# Switch-12v-PWM-4Ch.net
KiCad netlist of a schematic drawn in EAGLE
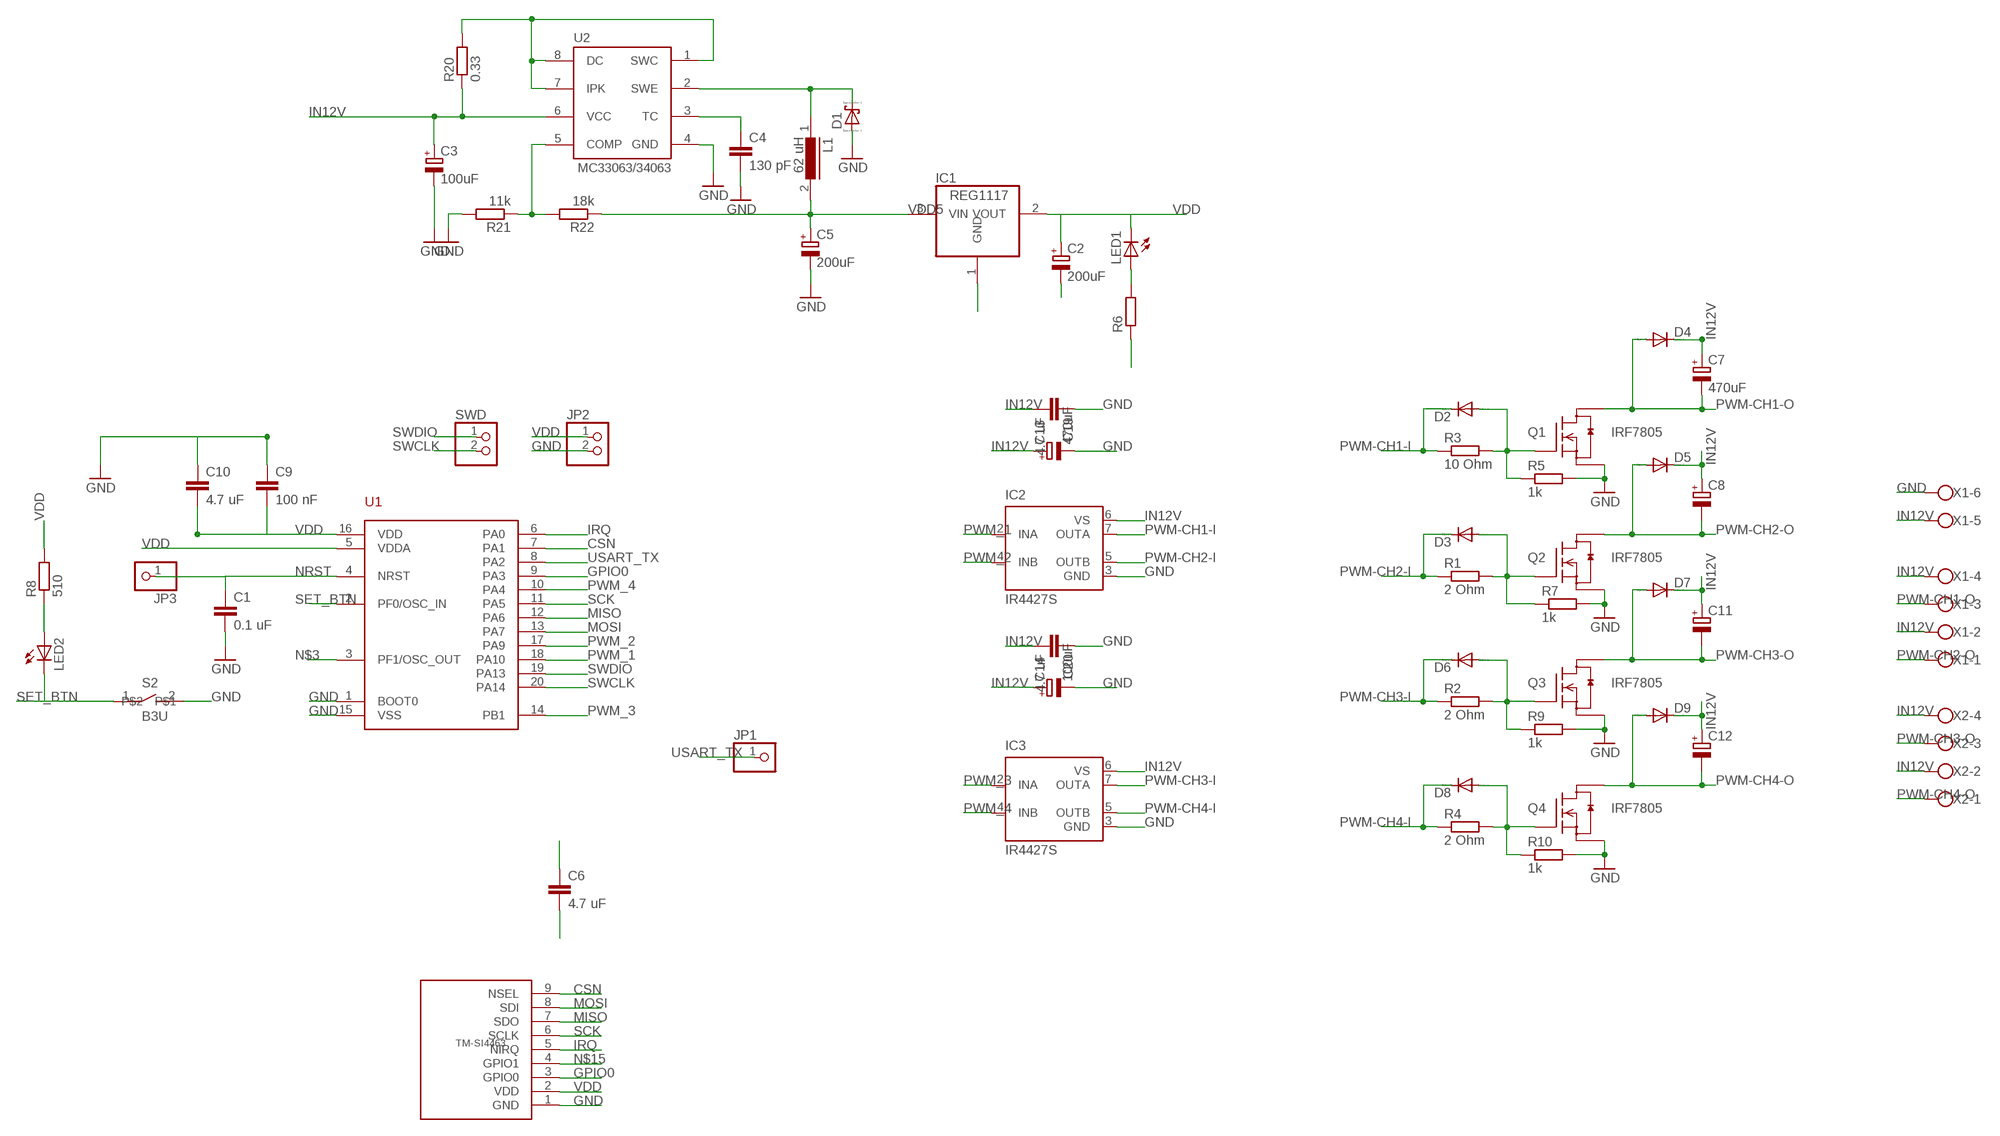
[diagram p0: schematic, sheet 1]

(export (version "E")
  (design (tool "Eeschema 10.0.6"))
  (components
    (comp (ref "C1")
      (value "0.1 uF")
      (footprint "eagle-import:C0805")
      (libsource (lib "eagle-import") (part "C-EUC0805"))
    )
    (comp (ref "C2")
      (value "200uF")
      (footprint "eagle-import:SMC_C")
      (libsource (lib "eagle-import") (part "CPOL-EUSMCC"))
    )
    (comp (ref "C3")
      (value "100uF")
      (footprint "eagle-import:SMC_C")
      (libsource (lib "eagle-import") (part "CPOL-EUSMCC"))
    )
    (comp (ref "C4")
      (value "130 pF")
      (footprint "eagle-import:C0805")
      (libsource (lib "eagle-import") (part "C-EUC0805"))
    )
    (comp (ref "C5")
      (value "200uF")
      (footprint "eagle-import:SMC_C")
      (libsource (lib "eagle-import") (part "CPOL-EUSMCC"))
    )
    (comp (ref "C6")
      (value "4.7 uF")
      (footprint "eagle-import:C0805")
      (libsource (lib "eagle-import") (part "C-EUC0805"))
    )
    (comp (ref "C7")
      (value "470uF")
      (footprint "eagle-import:E5-8,5")
      (libsource (lib "eagle-import") (part "CPOL-EUE5-8.5"))
    )
    (comp (ref "C8")
      (value "CPOL-EUE5-8.5")
      (footprint "eagle-import:E5-8,5")
      (libsource (lib "eagle-import") (part "CPOL-EUE5-8.5"))
    )
    (comp (ref "C9")
      (value "100 nF")
      (footprint "eagle-import:C0805")
      (libsource (lib "eagle-import") (part "C-EUC0805"))
    )
    (comp (ref "C10")
      (value "4.7 uF")
      (footprint "eagle-import:C0805")
      (libsource (lib "eagle-import") (part "C-EUC0805"))
    )
    (comp (ref "C11")
      (value "CPOL-EUE5-8.5")
      (footprint "eagle-import:E5-8,5")
      (libsource (lib "eagle-import") (part "CPOL-EUE5-8.5"))
    )
    (comp (ref "C12")
      (value "CPOL-EUE5-8.5")
      (footprint "eagle-import:E5-8,5")
      (libsource (lib "eagle-import") (part "CPOL-EUE5-8.5"))
    )
    (comp (ref "C13")
      (value "470uF")
      (footprint "eagle-import:085CS_1AR")
      (libsource (lib "eagle-import") (part "CPOL-EU085CS-1AR"))
    )
    (comp (ref "C14")
      (value "100uF")
      (footprint "eagle-import:085CS_1AR")
      (libsource (lib "eagle-import") (part "CPOL-EU085CS-1AR"))
    )
    (comp (ref "C19")
      (value "4.7 uF")
      (footprint "eagle-import:C0805")
      (libsource (lib "eagle-import") (part "C-EUC0805"))
    )
    (comp (ref "C20")
      (value "4.7 uF")
      (footprint "eagle-import:C0805")
      (libsource (lib "eagle-import") (part "C-EUC0805"))
    )
    (comp (ref "D1")
      (value "SCHOTTKY-DIODE")
      (footprint "eagle-import:DIODE_SMB")
      (libsource (lib "eagle-import") (part "SCHOTTKY-DIODE"))
    )
    (comp (ref "D2")
      (value "DIODE-DO214BA")
      (footprint "eagle-import:DO214BA")
      (libsource (lib "eagle-import") (part "DIODE-DO214BA"))
    )
    (comp (ref "D3")
      (value "DIODE-DO214BA")
      (footprint "eagle-import:DO214BA")
      (libsource (lib "eagle-import") (part "DIODE-DO214BA"))
    )
    (comp (ref "D4")
      (value "DIODE-DO214BA")
      (footprint "eagle-import:DO214BA")
      (libsource (lib "eagle-import") (part "DIODE-DO214BA"))
    )
    (comp (ref "D5")
      (value "DIODE-DO214BA")
      (footprint "eagle-import:DO214BA")
      (libsource (lib "eagle-import") (part "DIODE-DO214BA"))
    )
    (comp (ref "D6")
      (value "DIODE-DO214BA")
      (footprint "eagle-import:DO214BA")
      (libsource (lib "eagle-import") (part "DIODE-DO214BA"))
    )
    (comp (ref "D7")
      (value "DIODE-DO214BA")
      (footprint "eagle-import:DO214BA")
      (libsource (lib "eagle-import") (part "DIODE-DO214BA"))
    )
    (comp (ref "D8")
      (value "DIODE-DO214BA")
      (footprint "eagle-import:DO214BA")
      (libsource (lib "eagle-import") (part "DIODE-DO214BA"))
    )
    (comp (ref "D9")
      (value "DIODE-DO214BA")
      (footprint "eagle-import:DO214BA")
      (libsource (lib "eagle-import") (part "DIODE-DO214BA"))
    )
    (comp (ref "IC1")
      (value "REG1117")
      (footprint "eagle-import:SOT223")
      (libsource (lib "eagle-import") (part "REG1117"))
    )
    (comp (ref "IC2")
      (value "IR4427S")
      (footprint "eagle-import:SO08")
      (fields (field (name "MF") "INTERNATIONAL RECTIFIER(IR)") (field (name "MPN") "IR4427STRPBF"))
      (libsource (lib "eagle-import") (part "IR4427S"))
    )
    (comp (ref "IC3")
      (value "IR4427S")
      (footprint "eagle-import:SO08")
      (fields (field (name "MF") "INTERNATIONAL RECTIFIER(IR)") (field (name "MPN") "IR4427STRPBF"))
      (libsource (lib "eagle-import") (part "IR4427S"))
    )
    (comp (ref "JP1")
      (value "PINHD-1X1")
      (footprint "eagle-import:1X01")
      (libsource (lib "eagle-import") (part "PINHD-1X1"))
    )
    (comp (ref "JP2")
      (value "PINHD-1X2")
      (footprint "eagle-import:1X02")
      (libsource (lib "eagle-import") (part "PINHD-1X2"))
    )
    (comp (ref "JP3")
      (value "PINHD-1X1")
      (footprint "eagle-import:1X01")
      (libsource (lib "eagle-import") (part "PINHD-1X1"))
    )
    (comp (ref "L1")
      (value "62 uH")
      (footprint "eagle-import:DR73")
      (libsource (lib "eagle-import") (part "DR73"))
    )
    (comp (ref "LED1")
      (value "LEDCHIPLED_0805")
      (footprint "eagle-import:CHIPLED_0805")
      (libsource (lib "eagle-import") (part "LEDCHIPLED_0805"))
    )
    (comp (ref "LED2")
      (value "LEDCHIPLED_0805")
      (footprint "eagle-import:CHIPLED_0805")
      (libsource (lib "eagle-import") (part "LEDCHIPLED_0805"))
    )
    (comp (ref "Q1")
      (value "IRF7805")
      (footprint "eagle-import:SO-8")
      (libsource (lib "eagle-import") (part "IRF7805"))
    )
    (comp (ref "Q2")
      (value "IRF7805")
      (footprint "eagle-import:SO-8")
      (libsource (lib "eagle-import") (part "IRF7805"))
    )
    (comp (ref "Q3")
      (value "IRF7805")
      (footprint "eagle-import:SO-8")
      (libsource (lib "eagle-import") (part "IRF7805"))
    )
    (comp (ref "Q4")
      (value "IRF7805")
      (footprint "eagle-import:SO-8")
      (libsource (lib "eagle-import") (part "IRF7805"))
    )
    (comp (ref "R1")
      (value "2 Ohm")
      (footprint "eagle-import:R0805")
      (libsource (lib "eagle-import") (part "R-EU_R0805"))
    )
    (comp (ref "R2")
      (value "2 Ohm")
      (footprint "eagle-import:R0805")
      (libsource (lib "eagle-import") (part "R-EU_R0805"))
    )
    (comp (ref "R3")
      (value "10 Ohm")
      (footprint "eagle-import:R0805")
      (libsource (lib "eagle-import") (part "R-EU_R0805"))
    )
    (comp (ref "R4")
      (value "2 Ohm")
      (footprint "eagle-import:R0805")
      (libsource (lib "eagle-import") (part "R-EU_R0805"))
    )
    (comp (ref "R5")
      (value "1k")
      (footprint "eagle-import:R0805")
      (libsource (lib "eagle-import") (part "R-EU_R0805"))
    )
    (comp (ref "R6")
      (value "R-EU_R0805")
      (footprint "eagle-import:R0805")
      (libsource (lib "eagle-import") (part "R-EU_R0805"))
    )
    (comp (ref "R7")
      (value "1k")
      (footprint "eagle-import:R0805")
      (libsource (lib "eagle-import") (part "R-EU_R0805"))
    )
    (comp (ref "R8")
      (value "510")
      (footprint "eagle-import:R0805")
      (libsource (lib "eagle-import") (part "R-EU_R0805"))
    )
    (comp (ref "R9")
      (value "1k")
      (footprint "eagle-import:R0805")
      (libsource (lib "eagle-import") (part "R-EU_R0805"))
    )
    (comp (ref "R10")
      (value "1k")
      (footprint "eagle-import:R0805")
      (libsource (lib "eagle-import") (part "R-EU_R0805"))
    )
    (comp (ref "R20")
      (value "0.33")
      (footprint "eagle-import:R0805")
      (libsource (lib "eagle-import") (part "R-EU_R0805"))
    )
    (comp (ref "R21")
      (value "11k")
      (footprint "eagle-import:R0805")
      (libsource (lib "eagle-import") (part "R-EU_R0805"))
    )
    (comp (ref "R22")
      (value "18k")
      (footprint "eagle-import:R0805")
      (libsource (lib "eagle-import") (part "R-EU_R0805"))
    )
    (comp (ref "S2")
      (value "B3U")
      (footprint "eagle-import:1210")
      (libsource (lib "eagle-import") (part "B3U"))
    )
    (comp (ref "SWD")
      (value "PINHD-1X2")
      (footprint "eagle-import:1X02")
      (libsource (lib "eagle-import") (part "PINHD-1X2"))
    )
    (comp (ref "U$1")
      (value "TM-SI4463")
      (footprint "eagle-import:TM-SI4463-SMD")
      (libsource (lib "eagle-import") (part "TM-SI4463"))
    )
    (comp (ref "U1")
      (value "STM32F030F4")
      (footprint "eagle-import:TSSOP20")
      (libsource (lib "eagle-import") (part "STM32F030F4"))
    )
    (comp (ref "U2")
      (value "MC33063/MC34063D")
      (footprint "eagle-import:SO08")
      (libsource (lib "eagle-import") (part "MC33063/MC34063D"))
    )
    (comp (ref "X1")
      (value "W237-6")
      (footprint "eagle-import:W237-6")
      (libsource (lib "eagle-import") (part "W237-6"))
    )
    (comp (ref "X2")
      (value "W237-4")
      (footprint "eagle-import:W237-4")
      (libsource (lib "eagle-import") (part "W237-4"))
    )
  )
  (nets
    (net (code "1") (name "/CSN") (class "Default")
      (node (ref "U$1") (pin "9") (pinfunction "NSEL_9") (pintype "bidirectional"))
      (node (ref "U1") (pin "7") (pinfunction "PA1_7") (pintype "bidirectional"))
    )
    (net (code "2") (name "/GPIO0") (class "Default")
      (node (ref "U$1") (pin "3") (pinfunction "GPIO0_3") (pintype "bidirectional"))
      (node (ref "U1") (pin "9") (pinfunction "PA3_9") (pintype "bidirectional"))
    )
    (net (code "3") (name "/IN12V") (class "Default")
      (node (ref "C11") (pin "+") (pinfunction "+_+") (pintype "passive"))
      (node (ref "C12") (pin "+") (pinfunction "+_+") (pintype "passive"))
      (node (ref "C13") (pin "+") (pinfunction "+_+") (pintype "passive"))
      (node (ref "C14") (pin "+") (pinfunction "+_+") (pintype "passive"))
      (node (ref "C19") (pin "2") (pinfunction "2_2") (pintype "passive"))
      (node (ref "C20") (pin "2") (pinfunction "2_2") (pintype "passive"))
      (node (ref "C3") (pin "+") (pinfunction "+_+") (pintype "passive"))
      (node (ref "C7") (pin "+") (pinfunction "+_+") (pintype "passive"))
      (node (ref "C8") (pin "+") (pinfunction "+_+") (pintype "passive"))
      (node (ref "D4") (pin "C") (pinfunction "C_C") (pintype "passive"))
      (node (ref "D5") (pin "C") (pinfunction "C_C") (pintype "passive"))
      (node (ref "D7") (pin "C") (pinfunction "C_C") (pintype "passive"))
      (node (ref "D9") (pin "C") (pinfunction "C_C") (pintype "passive"))
      (node (ref "IC2") (pin "6") (pinfunction "VS_6") (pintype "power_in"))
      (node (ref "IC3") (pin "6") (pinfunction "VS_6") (pintype "power_in"))
      (node (ref "R20") (pin "1") (pinfunction "1_1") (pintype "passive"))
      (node (ref "U2") (pin "6") (pinfunction "VCC_6") (pintype "power_in"))
      (node (ref "X1") (pin "2") (pinfunction "KL_2") (pintype "passive"))
      (node (ref "X1") (pin "4") (pinfunction "KL_4") (pintype "passive"))
      (node (ref "X1") (pin "5") (pinfunction "KL_5") (pintype "passive"))
      (node (ref "X2") (pin "2") (pinfunction "KL_2") (pintype "passive"))
      (node (ref "X2") (pin "4") (pinfunction "KL_4") (pintype "passive"))
    )
    (net (code "4") (name "/IRQ") (class "Default")
      (node (ref "U$1") (pin "5") (pinfunction "NIRQ_5") (pintype "bidirectional"))
      (node (ref "U1") (pin "6") (pinfunction "PA0_6") (pintype "bidirectional"))
    )
    (net (code "5") (name "/MISO") (class "Default")
      (node (ref "U$1") (pin "7") (pinfunction "SDO_7") (pintype "bidirectional"))
      (node (ref "U1") (pin "12") (pinfunction "PA6_12") (pintype "bidirectional"))
    )
    (net (code "6") (name "/MOSI") (class "Default")
      (node (ref "U$1") (pin "8") (pinfunction "SDI_8") (pintype "bidirectional"))
      (node (ref "U1") (pin "13") (pinfunction "PA7_13") (pintype "bidirectional"))
    )
    (net (code "7") (name "/N$3") (class "Default")
      (node (ref "U1") (pin "3") (pinfunction "PF1/OSC_OUT_3") (pintype "bidirectional"))
    )
    (net (code "8") (name "/N$15") (class "Default")
      (node (ref "U$1") (pin "4") (pinfunction "GPIO1_4") (pintype "bidirectional"))
    )
    (net (code "9") (name "/NRST") (class "Default")
      (node (ref "C1") (pin "1") (pinfunction "1_1") (pintype "passive"))
      (node (ref "JP3") (pin "1") (pinfunction "1_1") (pintype "passive"))
      (node (ref "U1") (pin "4") (pinfunction "NRST_4") (pintype "bidirectional"))
    )
    (net (code "10") (name "/PWM-CH1-I") (class "Default")
      (node (ref "D2") (pin "C") (pinfunction "C_C") (pintype "passive"))
      (node (ref "IC2") (pin "7") (pinfunction "OUTA_7") (pintype "output"))
      (node (ref "R3") (pin "1") (pinfunction "1_1") (pintype "passive"))
    )
    (net (code "11") (name "/PWM-CH1-O") (class "Default")
      (node (ref "C7") (pin "-") (pinfunction "-_-") (pintype "passive"))
      (node (ref "D4") (pin "A") (pinfunction "A_A") (pintype "passive"))
      (node (ref "Q1") (pin "8") (pinfunction "D_8") (pintype "passive"))
      (node (ref "X1") (pin "3") (pinfunction "KL_3") (pintype "passive"))
    )
    (net (code "12") (name "/PWM-CH2-I") (class "Default")
      (node (ref "D3") (pin "C") (pinfunction "C_C") (pintype "passive"))
      (node (ref "IC2") (pin "5") (pinfunction "OUTB_5") (pintype "output"))
      (node (ref "R1") (pin "1") (pinfunction "1_1") (pintype "passive"))
    )
    (net (code "13") (name "/PWM-CH2-O") (class "Default")
      (node (ref "C8") (pin "-") (pinfunction "-_-") (pintype "passive"))
      (node (ref "D5") (pin "A") (pinfunction "A_A") (pintype "passive"))
      (node (ref "Q2") (pin "8") (pinfunction "D_8") (pintype "passive"))
      (node (ref "X1") (pin "1") (pinfunction "KL_1") (pintype "passive"))
    )
    (net (code "14") (name "/PWM-CH3-I") (class "Default")
      (node (ref "D6") (pin "C") (pinfunction "C_C") (pintype "passive"))
      (node (ref "IC3") (pin "7") (pinfunction "OUTA_7") (pintype "output"))
      (node (ref "R2") (pin "1") (pinfunction "1_1") (pintype "passive"))
    )
    (net (code "15") (name "/PWM-CH3-O") (class "Default")
      (node (ref "C11") (pin "-") (pinfunction "-_-") (pintype "passive"))
      (node (ref "D7") (pin "A") (pinfunction "A_A") (pintype "passive"))
      (node (ref "Q3") (pin "8") (pinfunction "D_8") (pintype "passive"))
      (node (ref "X2") (pin "3") (pinfunction "KL_3") (pintype "passive"))
    )
    (net (code "16") (name "/PWM-CH4-I") (class "Default")
      (node (ref "D8") (pin "C") (pinfunction "C_C") (pintype "passive"))
      (node (ref "IC3") (pin "5") (pinfunction "OUTB_5") (pintype "output"))
      (node (ref "R4") (pin "1") (pinfunction "1_1") (pintype "passive"))
    )
    (net (code "17") (name "/PWM-CH4-O") (class "Default")
      (node (ref "C12") (pin "-") (pinfunction "-_-") (pintype "passive"))
      (node (ref "D9") (pin "A") (pinfunction "A_A") (pintype "passive"))
      (node (ref "Q4") (pin "8") (pinfunction "D_8") (pintype "passive"))
      (node (ref "X2") (pin "1") (pinfunction "KL_1") (pintype "passive"))
    )
    (net (code "18") (name "/PWM_1") (class "Default")
      (node (ref "IC2") (pin "2") (pinfunction "INA_2") (pintype "input"))
      (node (ref "U1") (pin "18") (pinfunction "PA10_18") (pintype "bidirectional"))
    )
    (net (code "19") (name "/PWM_2") (class "Default")
      (node (ref "IC2") (pin "4") (pinfunction "INB_4") (pintype "input"))
      (node (ref "U1") (pin "17") (pinfunction "PA9_17") (pintype "bidirectional"))
    )
    (net (code "20") (name "/PWM_3") (class "Default")
      (node (ref "IC3") (pin "2") (pinfunction "INA_2") (pintype "input"))
      (node (ref "U1") (pin "14") (pinfunction "PB1_14") (pintype "bidirectional"))
    )
    (net (code "21") (name "/PWM_4") (class "Default")
      (node (ref "IC3") (pin "4") (pinfunction "INB_4") (pintype "input"))
      (node (ref "U1") (pin "10") (pinfunction "PA4_10") (pintype "bidirectional"))
    )
    (net (code "22") (name "/SCK") (class "Default")
      (node (ref "U$1") (pin "6") (pinfunction "SCLK_6") (pintype "bidirectional"))
      (node (ref "U1") (pin "11") (pinfunction "PA5_11") (pintype "bidirectional"))
    )
    (net (code "23") (name "/SET_BTN") (class "Default")
      (node (ref "LED2") (pin "C") (pinfunction "C_C") (pintype "passive"))
      (node (ref "S2") (pin "1") (pinfunction "P$1_1") (pintype "power_in"))
      (node (ref "U1") (pin "2") (pinfunction "PF0/OSC_IN_2") (pintype "bidirectional"))
    )
    (net (code "24") (name "/SWCLK") (class "Default")
      (node (ref "SWD") (pin "2") (pinfunction "2_2") (pintype "passive"))
      (node (ref "U1") (pin "20") (pinfunction "PA14_20") (pintype "bidirectional"))
    )
    (net (code "25") (name "/SWDIO") (class "Default")
      (node (ref "SWD") (pin "1") (pinfunction "1_1") (pintype "passive"))
      (node (ref "U1") (pin "19") (pinfunction "PA13_19") (pintype "bidirectional"))
    )
    (net (code "26") (name "/USART_TX") (class "Default")
      (node (ref "JP1") (pin "1") (pinfunction "1_1") (pintype "passive"))
      (node (ref "U1") (pin "8") (pinfunction "PA2_8") (pintype "bidirectional"))
    )
    (net (code "27") (name "/VDD") (class "Default")
      (node (ref "C10") (pin "2") (pinfunction "2_2") (pintype "passive"))
      (node (ref "C2") (pin "+") (pinfunction "+_+") (pintype "passive"))
      (node (ref "C6") (pin "1") (pinfunction "1_1") (pintype "passive"))
      (node (ref "C9") (pin "2") (pinfunction "2_2") (pintype "passive"))
      (node (ref "IC1") (pin "2") (pinfunction "VOUT_2") (pintype "output"))
      (node (ref "JP2") (pin "1") (pinfunction "1_1") (pintype "passive"))
      (node (ref "LED1") (pin "C") (pinfunction "C_C") (pintype "passive"))
      (node (ref "R8") (pin "2") (pinfunction "2_2") (pintype "passive"))
      (node (ref "U$1") (pin "2") (pinfunction "VDD_2") (pintype "power_in"))
      (node (ref "U1") (pin "16") (pinfunction "VDD_16") (pintype "bidirectional"))
      (node (ref "U1") (pin "5") (pinfunction "VDDA_5") (pintype "bidirectional"))
    )
    (net (code "28") (name "/VDD5") (class "Default")
      (node (ref "C5") (pin "+") (pinfunction "+_+") (pintype "passive"))
      (node (ref "IC1") (pin "3") (pinfunction "VIN_3") (pintype "input"))
      (node (ref "L1") (pin "2") (pinfunction "2_2") (pintype "passive"))
      (node (ref "R22") (pin "1") (pinfunction "1_1") (pintype "passive"))
    )
    (net (code "29") (name "GND") (class "Default")
      (node (ref "C1") (pin "2") (pinfunction "2_2") (pintype "passive"))
      (node (ref "C10") (pin "1") (pinfunction "1_1") (pintype "passive"))
      (node (ref "C13") (pin "-") (pinfunction "-_-") (pintype "passive"))
      (node (ref "C14") (pin "-") (pinfunction "-_-") (pintype "passive"))
      (node (ref "C19") (pin "1") (pinfunction "1_1") (pintype "passive"))
      (node (ref "C2") (pin "-") (pinfunction "-_-") (pintype "passive"))
      (node (ref "C20") (pin "1") (pinfunction "1_1") (pintype "passive"))
      (node (ref "C3") (pin "-") (pinfunction "-_-") (pintype "passive"))
      (node (ref "C4") (pin "2") (pinfunction "2_2") (pintype "passive"))
      (node (ref "C5") (pin "-") (pinfunction "-_-") (pintype "passive"))
      (node (ref "C6") (pin "2") (pinfunction "2_2") (pintype "passive"))
      (node (ref "C9") (pin "1") (pinfunction "1_1") (pintype "passive"))
      (node (ref "D1") (pin "A") (pinfunction "C_A") (pintype "passive"))
      (node (ref "IC1") (pin "1") (pinfunction "GND_1") (pintype "power_in"))
      (node (ref "IC2") (pin "3") (pinfunction "GND_3") (pintype "power_in"))
      (node (ref "IC3") (pin "3") (pinfunction "GND_3") (pintype "power_in"))
      (node (ref "JP2") (pin "2") (pinfunction "2_2") (pintype "passive"))
      (node (ref "Q1") (pin "3") (pinfunction "S_3") (pintype "passive"))
      (node (ref "Q2") (pin "3") (pinfunction "S_3") (pintype "passive"))
      (node (ref "Q3") (pin "3") (pinfunction "S_3") (pintype "passive"))
      (node (ref "Q4") (pin "3") (pinfunction "S_3") (pintype "passive"))
      (node (ref "R10") (pin "2") (pinfunction "2_2") (pintype "passive"))
      (node (ref "R21") (pin "2") (pinfunction "2_2") (pintype "passive"))
      (node (ref "R5") (pin "2") (pinfunction "2_2") (pintype "passive"))
      (node (ref "R6") (pin "1") (pinfunction "1_1") (pintype "passive"))
      (node (ref "R7") (pin "2") (pinfunction "2_2") (pintype "passive"))
      (node (ref "R9") (pin "2") (pinfunction "2_2") (pintype "passive"))
      (node (ref "S2") (pin "2") (pinfunction "P$2_2") (pintype "power_in"))
      (node (ref "U$1") (pin "1") (pinfunction "GND_1") (pintype "power_in"))
      (node (ref "U1") (pin "1") (pinfunction "BOOT0_1") (pintype "bidirectional"))
      (node (ref "U1") (pin "15") (pinfunction "VSS_15") (pintype "bidirectional"))
      (node (ref "U2") (pin "4") (pinfunction "GND_4") (pintype "power_in"))
      (node (ref "X1") (pin "6") (pinfunction "KL_6") (pintype "passive"))
    )
    (net (code "30") (name "Net-(D1-A)") (class "Default")
      (node (ref "D1") (pin "C") (pinfunction "A_C") (pintype "passive"))
      (node (ref "L1") (pin "1") (pinfunction "1_1") (pintype "passive"))
      (node (ref "U2") (pin "2") (pinfunction "SWE_2") (pintype "input"))
    )
    (net (code "31") (name "Net-(LED1-PadA)") (class "Default")
      (node (ref "LED1") (pin "A") (pinfunction "A_A") (pintype "passive"))
      (node (ref "R6") (pin "2") (pinfunction "2_2") (pintype "passive"))
    )
    (net (code "32") (name "Net-(LED2-PadA)") (class "Default")
      (node (ref "LED2") (pin "A") (pinfunction "A_A") (pintype "passive"))
      (node (ref "R8") (pin "1") (pinfunction "1_1") (pintype "passive"))
    )
    (net (code "33") (name "Net-(Q1-G)") (class "Default")
      (node (ref "D2") (pin "A") (pinfunction "A_A") (pintype "passive"))
      (node (ref "Q1") (pin "4") (pinfunction "G_4") (pintype "passive"))
      (node (ref "R3") (pin "2") (pinfunction "2_2") (pintype "passive"))
      (node (ref "R5") (pin "1") (pinfunction "1_1") (pintype "passive"))
    )
    (net (code "34") (name "Net-(Q2-G)") (class "Default")
      (node (ref "D3") (pin "A") (pinfunction "A_A") (pintype "passive"))
      (node (ref "Q2") (pin "4") (pinfunction "G_4") (pintype "passive"))
      (node (ref "R1") (pin "2") (pinfunction "2_2") (pintype "passive"))
      (node (ref "R7") (pin "1") (pinfunction "1_1") (pintype "passive"))
    )
    (net (code "35") (name "Net-(Q3-G)") (class "Default")
      (node (ref "D6") (pin "A") (pinfunction "A_A") (pintype "passive"))
      (node (ref "Q3") (pin "4") (pinfunction "G_4") (pintype "passive"))
      (node (ref "R2") (pin "2") (pinfunction "2_2") (pintype "passive"))
      (node (ref "R9") (pin "1") (pinfunction "1_1") (pintype "passive"))
    )
    (net (code "36") (name "Net-(Q4-G)") (class "Default")
      (node (ref "D8") (pin "A") (pinfunction "A_A") (pintype "passive"))
      (node (ref "Q4") (pin "4") (pinfunction "G_4") (pintype "passive"))
      (node (ref "R10") (pin "1") (pinfunction "1_1") (pintype "passive"))
      (node (ref "R4") (pin "2") (pinfunction "2_2") (pintype "passive"))
    )
    (net (code "37") (name "Net-(U2-COMP)") (class "Default")
      (node (ref "R21") (pin "1") (pinfunction "1_1") (pintype "passive"))
      (node (ref "R22") (pin "2") (pinfunction "2_2") (pintype "passive"))
      (node (ref "U2") (pin "5") (pinfunction "COMP_5") (pintype "input"))
    )
    (net (code "38") (name "Net-(U2-DC)") (class "Default")
      (node (ref "R20") (pin "2") (pinfunction "2_2") (pintype "passive"))
      (node (ref "U2") (pin "1") (pinfunction "SWC_1") (pintype "input"))
      (node (ref "U2") (pin "7") (pinfunction "IPK_7") (pintype "bidirectional"))
      (node (ref "U2") (pin "8") (pinfunction "DC_8") (pintype "input"))
    )
    (net (code "39") (name "Net-(U2-TC)") (class "Default")
      (node (ref "C4") (pin "1") (pinfunction "1_1") (pintype "passive"))
      (node (ref "U2") (pin "3") (pinfunction "TC_3") (pintype "input"))
    )
    (net (code "40") (name "unconnected-(Q1-D-Pad5)") (class "Default")
      (node (ref "Q1") (pin "5") (pinfunction "D_5") (pintype "passive"))
    )
    (net (code "41") (name "unconnected-(Q1-D-Pad6)") (class "Default")
      (node (ref "Q1") (pin "6") (pinfunction "D_6") (pintype "passive"))
    )
    (net (code "42") (name "unconnected-(Q1-D-Pad7)") (class "Default")
      (node (ref "Q1") (pin "7") (pinfunction "D_7") (pintype "passive"))
    )
    (net (code "43") (name "unconnected-(Q1-S-Pad1)") (class "Default")
      (node (ref "Q1") (pin "1") (pinfunction "S_1") (pintype "passive"))
    )
    (net (code "44") (name "unconnected-(Q1-S-Pad2)") (class "Default")
      (node (ref "Q1") (pin "2") (pinfunction "S_2") (pintype "passive"))
    )
    (net (code "45") (name "unconnected-(Q2-D-Pad5)") (class "Default")
      (node (ref "Q2") (pin "5") (pinfunction "D_5") (pintype "passive"))
    )
    (net (code "46") (name "unconnected-(Q2-D-Pad6)") (class "Default")
      (node (ref "Q2") (pin "6") (pinfunction "D_6") (pintype "passive"))
    )
    (net (code "47") (name "unconnected-(Q2-D-Pad7)") (class "Default")
      (node (ref "Q2") (pin "7") (pinfunction "D_7") (pintype "passive"))
    )
    (net (code "48") (name "unconnected-(Q2-S-Pad1)") (class "Default")
      (node (ref "Q2") (pin "1") (pinfunction "S_1") (pintype "passive"))
    )
    (net (code "49") (name "unconnected-(Q2-S-Pad2)") (class "Default")
      (node (ref "Q2") (pin "2") (pinfunction "S_2") (pintype "passive"))
    )
    (net (code "50") (name "unconnected-(Q3-D-Pad5)") (class "Default")
      (node (ref "Q3") (pin "5") (pinfunction "D_5") (pintype "passive"))
    )
    (net (code "51") (name "unconnected-(Q3-D-Pad6)") (class "Default")
      (node (ref "Q3") (pin "6") (pinfunction "D_6") (pintype "passive"))
    )
    (net (code "52") (name "unconnected-(Q3-D-Pad7)") (class "Default")
      (node (ref "Q3") (pin "7") (pinfunction "D_7") (pintype "passive"))
    )
    (net (code "53") (name "unconnected-(Q3-S-Pad1)") (class "Default")
      (node (ref "Q3") (pin "1") (pinfunction "S_1") (pintype "passive"))
    )
    (net (code "54") (name "unconnected-(Q3-S-Pad2)") (class "Default")
      (node (ref "Q3") (pin "2") (pinfunction "S_2") (pintype "passive"))
    )
    (net (code "55") (name "unconnected-(Q4-D-Pad5)") (class "Default")
      (node (ref "Q4") (pin "5") (pinfunction "D_5") (pintype "passive"))
    )
    (net (code "56") (name "unconnected-(Q4-D-Pad6)") (class "Default")
      (node (ref "Q4") (pin "6") (pinfunction "D_6") (pintype "passive"))
    )
    (net (code "57") (name "unconnected-(Q4-D-Pad7)") (class "Default")
      (node (ref "Q4") (pin "7") (pinfunction "D_7") (pintype "passive"))
    )
    (net (code "58") (name "unconnected-(Q4-S-Pad1)") (class "Default")
      (node (ref "Q4") (pin "1") (pinfunction "S_1") (pintype "passive"))
    )
    (net (code "59") (name "unconnected-(Q4-S-Pad2)") (class "Default")
      (node (ref "Q4") (pin "2") (pinfunction "S_2") (pintype "passive"))
    )
  )
)
